# ftdi_modbus_v2.net
KiCad netlist of a schematic drawn in EAGLE
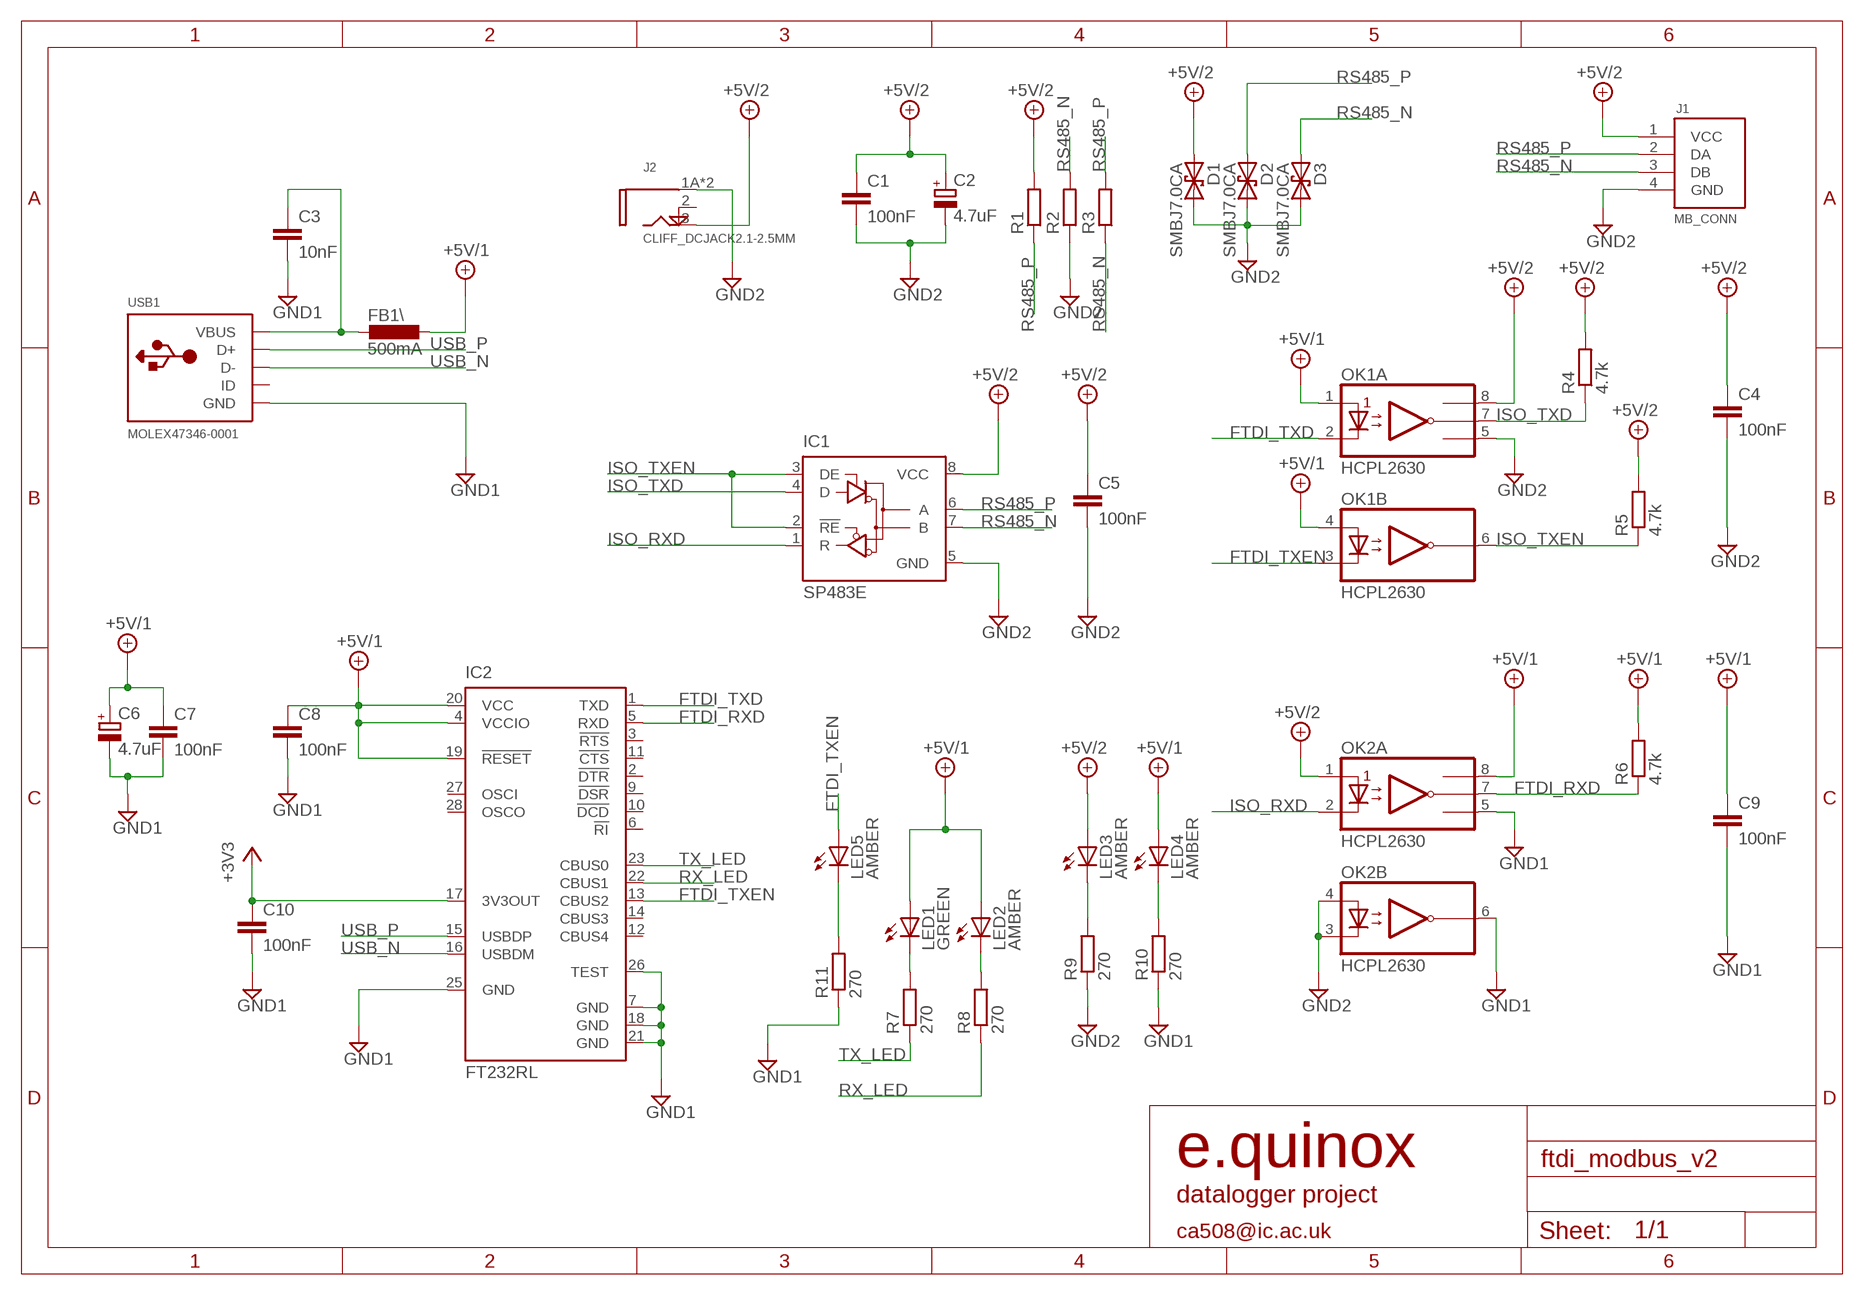
[diagram p0: schematic, sheet 1]

(export (version "E")
  (design (tool "Eeschema 10.0.6"))
  (components
    (comp (ref "C1")
      (value "100nF")
      (footprint "eagle-import:C0603")
      (libsource (lib "eagle-import") (part "C-EUC0603"))
    )
    (comp (ref "C2")
      (value "4.7uF")
      (footprint "eagle-import:B_3528-21R")
      (libsource (lib "eagle-import") (part "CPOL-EUB/3528-21R"))
    )
    (comp (ref "C3")
      (value "10nF")
      (footprint "eagle-import:C0603")
      (libsource (lib "eagle-import") (part "C-EUC0603"))
    )
    (comp (ref "C4")
      (value "100nF")
      (footprint "eagle-import:C1206")
      (libsource (lib "eagle-import") (part "C-EUC1206"))
    )
    (comp (ref "C5")
      (value "100nF")
      (footprint "eagle-import:C0603")
      (libsource (lib "eagle-import") (part "C-EUC0603"))
    )
    (comp (ref "C6")
      (value "4.7uF")
      (footprint "eagle-import:B_3528-21R")
      (libsource (lib "eagle-import") (part "CPOL-EUB/3528-21R"))
    )
    (comp (ref "C7")
      (value "100nF")
      (footprint "eagle-import:C0603")
      (libsource (lib "eagle-import") (part "C-EUC0603"))
    )
    (comp (ref "C8")
      (value "100nF")
      (footprint "eagle-import:C0603")
      (libsource (lib "eagle-import") (part "C-EUC0603"))
    )
    (comp (ref "C9")
      (value "100nF")
      (footprint "eagle-import:C1206")
      (libsource (lib "eagle-import") (part "C-EUC1206"))
    )
    (comp (ref "C10")
      (value "100nF")
      (footprint "eagle-import:C0603")
      (libsource (lib "eagle-import") (part "C-EUC0603"))
    )
    (comp (ref "D1")
      (value "SMBJ7.0CA")
      (footprint "eagle-import:DO214AA")
      (libsource (lib "eagle-import") (part "SMBJ7.0CA"))
    )
    (comp (ref "D2")
      (value "SMBJ7.0CA")
      (footprint "eagle-import:DO214AA")
      (libsource (lib "eagle-import") (part "SMBJ7.0CA"))
    )
    (comp (ref "D3")
      (value "SMBJ7.0CA")
      (footprint "eagle-import:DO214AA")
      (libsource (lib "eagle-import") (part "SMBJ7.0CA"))
    )
    (comp (ref "FB1\\")
      (value "500mA")
      (footprint "eagle-import:L3216C")
      (libsource (lib "eagle-import") (part "L-EUL3216C"))
    )
    (comp (ref "IC1")
      (value "SP483E")
      (footprint "eagle-import:D_R-PDSO-G8")
      (libsource (lib "eagle-import") (part "75176AD"))
    )
    (comp (ref "IC2")
      (value "FT232RL")
      (footprint "eagle-import:SSOP28")
      (libsource (lib "eagle-import") (part "FT232RL"))
    )
    (comp (ref "J1")
      (value "MB_CONN")
      (footprint "eagle-import:PTSM0,5_4-HH-2,5-THR")
      (libsource (lib "eagle-import") (part "MB_CONN"))
    )
    (comp (ref "J2")
      (value "CLIFF_DCJACK2.1-2.5MM")
      (footprint "eagle-import:FC6814XS")
      (libsource (lib "eagle-import") (part "CLIFF_DCJACK2.1-2.5MM"))
    )
    (comp (ref "LED1")
      (value "GREEN")
      (footprint "eagle-import:CHIPLED_0805")
      (libsource (lib "eagle-import") (part "LEDCHIPLED_0805"))
    )
    (comp (ref "LED2")
      (value "AMBER")
      (footprint "eagle-import:CHIPLED_0805")
      (libsource (lib "eagle-import") (part "LEDCHIPLED_0805"))
    )
    (comp (ref "LED3")
      (value "AMBER")
      (footprint "eagle-import:CHIPLED_0805")
      (libsource (lib "eagle-import") (part "LEDCHIPLED_0805"))
    )
    (comp (ref "LED4")
      (value "AMBER")
      (footprint "eagle-import:CHIPLED_0805")
      (libsource (lib "eagle-import") (part "LEDCHIPLED_0805"))
    )
    (comp (ref "LED5")
      (value "AMBER")
      (footprint "eagle-import:CHIPLED_0805")
      (libsource (lib "eagle-import") (part "LEDCHIPLED_0805"))
    )
    (comp (ref "OK1")
      (value "HCPL2630")
      (footprint "eagle-import:DIL08")
      (fields (field (name "MF") "AGILENT TECHNOLOGIES") (field (name "MPN") "HCPL-2630-000E"))
      (libsource (lib "eagle-import") (part "HCPL2630"))
    )
    (comp (ref "OK2")
      (value "HCPL2630")
      (footprint "eagle-import:DIL08")
      (fields (field (name "MF") "AGILENT TECHNOLOGIES") (field (name "MPN") "HCPL-2630-000E"))
      (libsource (lib "eagle-import") (part "HCPL2630"))
    )
    (comp (ref "R1")
      (value "R-EU_0207/10")
      (footprint "eagle-import:0207_10")
      (libsource (lib "eagle-import") (part "R-EU_0207/10"))
    )
    (comp (ref "R2")
      (value "R-EU_0207/10")
      (footprint "eagle-import:0207_10")
      (libsource (lib "eagle-import") (part "R-EU_0207/10"))
    )
    (comp (ref "R3")
      (value "R-EU_0207/10")
      (footprint "eagle-import:0207_10")
      (libsource (lib "eagle-import") (part "R-EU_0207/10"))
    )
    (comp (ref "R4")
      (value "4.7k")
      (footprint "eagle-import:M0805")
      (libsource (lib "eagle-import") (part "R-EU_M0805"))
    )
    (comp (ref "R5")
      (value "4.7k")
      (footprint "eagle-import:M0805")
      (libsource (lib "eagle-import") (part "R-EU_M0805"))
    )
    (comp (ref "R6")
      (value "4.7k")
      (footprint "eagle-import:M0805")
      (libsource (lib "eagle-import") (part "R-EU_M0805"))
    )
    (comp (ref "R7")
      (value "270")
      (footprint "eagle-import:M0805")
      (libsource (lib "eagle-import") (part "R-EU_M0805"))
    )
    (comp (ref "R8")
      (value "270")
      (footprint "eagle-import:M0805")
      (libsource (lib "eagle-import") (part "R-EU_M0805"))
    )
    (comp (ref "R9")
      (value "270")
      (footprint "eagle-import:M0805")
      (libsource (lib "eagle-import") (part "R-EU_M0805"))
    )
    (comp (ref "R10")
      (value "270")
      (footprint "eagle-import:M0805")
      (libsource (lib "eagle-import") (part "R-EU_M0805"))
    )
    (comp (ref "R11")
      (value "270")
      (footprint "eagle-import:M0805")
      (libsource (lib "eagle-import") (part "R-EU_M0805"))
    )
    (comp (ref "USB1")
      (value "MOLEX47346-0001")
      (footprint "eagle-import:47346-0001")
      (libsource (lib "eagle-import") (part "MOLEX47346-0001"))
    )
  )
  (nets
    (net (code "1") (name "+3V3") (class "Default")
      (node (ref "C10") (pin "1") (pinfunction "1_1") (pintype "passive"))
      (node (ref "IC2") (pin "17") (pinfunction "3V3OUT_17") (pintype "output"))
    )
    (net (code "2") (name "+5V{slash}1") (class "Default")
      (node (ref "C6") (pin "+") (pinfunction "+_+") (pintype "passive"))
      (node (ref "C7") (pin "1") (pinfunction "1_1") (pintype "passive"))
      (node (ref "C8") (pin "1") (pinfunction "1_1") (pintype "passive"))
      (node (ref "C9") (pin "1") (pinfunction "1_1") (pintype "passive"))
      (node (ref "FB1\\") (pin "1") (pinfunction "1_1") (pintype "passive"))
      (node (ref "IC2") (pin "19") (pinfunction "~{RESET}_19") (pintype "input"))
      (node (ref "IC2") (pin "20") (pinfunction "VCC_20") (pintype "power_in"))
      (node (ref "IC2") (pin "4") (pinfunction "VCCIO_4") (pintype "power_in"))
      (node (ref "LED1") (pin "A") (pinfunction "A_A") (pintype "passive"))
      (node (ref "LED2") (pin "A") (pinfunction "A_A") (pintype "passive"))
      (node (ref "LED4") (pin "A") (pinfunction "A_A") (pintype "passive"))
      (node (ref "OK1") (pin "1") (pinfunction "A1_1") (pintype "passive"))
      (node (ref "OK1") (pin "4") (pinfunction "A2_4") (pintype "passive"))
      (node (ref "OK2") (pin "8") (pinfunction "VCC_8") (pintype "passive"))
      (node (ref "R6") (pin "2") (pinfunction "2_2") (pintype "passive"))
    )
    (net (code "3") (name "+5V{slash}2") (class "Default")
      (node (ref "C1") (pin "1") (pinfunction "1_1") (pintype "passive"))
      (node (ref "C2") (pin "+") (pinfunction "+_+") (pintype "passive"))
      (node (ref "C4") (pin "1") (pinfunction "1_1") (pintype "passive"))
      (node (ref "C5") (pin "1") (pinfunction "1_1") (pintype "passive"))
      (node (ref "D1") (pin "P$1") (pinfunction "1_P$1") (pintype "passive"))
      (node (ref "IC1") (pin "8") (pinfunction "VCC_8") (pintype "power_in"))
      (node (ref "J1") (pin "1") (pinfunction "VCC_1") (pintype "power_in"))
      (node (ref "J2") (pin "3") (pinfunction "TIP_3") (pintype "power_in"))
      (node (ref "LED3") (pin "A") (pinfunction "A_A") (pintype "passive"))
      (node (ref "OK1") (pin "8") (pinfunction "VCC_8") (pintype "passive"))
      (node (ref "OK2") (pin "1") (pinfunction "A1_1") (pintype "passive"))
      (node (ref "R1") (pin "2") (pinfunction "2_2") (pintype "passive"))
      (node (ref "R4") (pin "2") (pinfunction "2_2") (pintype "passive"))
      (node (ref "R5") (pin "2") (pinfunction "2_2") (pintype "passive"))
    )
    (net (code "4") (name "/FTDI_RXD") (class "Default")
      (node (ref "IC2") (pin "5") (pinfunction "RXD_5") (pintype "input"))
      (node (ref "OK2") (pin "7") (pinfunction "VO1_7") (pintype "passive"))
      (node (ref "R6") (pin "1") (pinfunction "1_1") (pintype "passive"))
    )
    (net (code "5") (name "/FTDI_TXD") (class "Default")
      (node (ref "IC2") (pin "1") (pinfunction "TXD_1") (pintype "output"))
      (node (ref "OK1") (pin "2") (pinfunction "C1_2") (pintype "passive"))
    )
    (net (code "6") (name "/FTDI_TXEN") (class "Default")
      (node (ref "IC2") (pin "13") (pinfunction "CBUS2_13") (pintype "bidirectional"))
      (node (ref "LED5") (pin "A") (pinfunction "A_A") (pintype "passive"))
      (node (ref "OK1") (pin "3") (pinfunction "C2_3") (pintype "passive"))
    )
    (net (code "7") (name "/ISO_RXD") (class "Default")
      (node (ref "IC1") (pin "1") (pinfunction "R_1") (pintype "input"))
      (node (ref "OK2") (pin "2") (pinfunction "C1_2") (pintype "passive"))
    )
    (net (code "8") (name "/ISO_TXD") (class "Default")
      (node (ref "IC1") (pin "4") (pinfunction "D_4") (pintype "input"))
      (node (ref "OK1") (pin "7") (pinfunction "VO1_7") (pintype "passive"))
      (node (ref "R4") (pin "1") (pinfunction "1_1") (pintype "passive"))
    )
    (net (code "9") (name "/ISO_TXEN") (class "Default")
      (node (ref "IC1") (pin "2") (pinfunction "~{RE}_2") (pintype "input"))
      (node (ref "IC1") (pin "3") (pinfunction "DE_3") (pintype "input"))
      (node (ref "OK1") (pin "6") (pinfunction "VO2_6") (pintype "passive"))
      (node (ref "R5") (pin "1") (pinfunction "1_1") (pintype "passive"))
    )
    (net (code "10") (name "/RS485_N") (class "Default")
      (node (ref "D3") (pin "P$1") (pinfunction "1_P$1") (pintype "passive"))
      (node (ref "IC1") (pin "7") (pinfunction "B_7") (pintype "output"))
      (node (ref "J1") (pin "3") (pinfunction "DB_3") (pintype "bidirectional"))
      (node (ref "R2") (pin "2") (pinfunction "2_2") (pintype "passive"))
      (node (ref "R3") (pin "1") (pinfunction "1_1") (pintype "passive"))
    )
    (net (code "11") (name "/RS485_P") (class "Default")
      (node (ref "D2") (pin "P$1") (pinfunction "1_P$1") (pintype "passive"))
      (node (ref "IC1") (pin "6") (pinfunction "A_6") (pintype "output"))
      (node (ref "J1") (pin "2") (pinfunction "DA_2") (pintype "bidirectional"))
      (node (ref "R1") (pin "1") (pinfunction "1_1") (pintype "passive"))
      (node (ref "R3") (pin "2") (pinfunction "2_2") (pintype "passive"))
    )
    (net (code "12") (name "/RX_LED") (class "Default")
      (node (ref "IC2") (pin "22") (pinfunction "CBUS1_22") (pintype "bidirectional"))
      (node (ref "R8") (pin "1") (pinfunction "1_1") (pintype "passive"))
    )
    (net (code "13") (name "/SHUNT") (class "Default")
      (node (ref "J2") (pin "2") (pinfunction "SHUNT_2") (pintype "power_in"))
    )
    (net (code "14") (name "/TX_LED") (class "Default")
      (node (ref "IC2") (pin "23") (pinfunction "CBUS0_23") (pintype "bidirectional"))
      (node (ref "R7") (pin "1") (pinfunction "1_1") (pintype "passive"))
    )
    (net (code "15") (name "/USB_N") (class "Default")
      (node (ref "IC2") (pin "16") (pinfunction "USBDM_16") (pintype "bidirectional"))
      (node (ref "USB1") (pin "2") (pinfunction "D-_2") (pintype "bidirectional"))
    )
    (net (code "16") (name "/USB_P") (class "Default")
      (node (ref "IC2") (pin "15") (pinfunction "USBDP_15") (pintype "bidirectional"))
      (node (ref "USB1") (pin "3") (pinfunction "D+_3") (pintype "bidirectional"))
    )
    (net (code "17") (name "GND1") (class "Default")
      (node (ref "C10") (pin "2") (pinfunction "2_2") (pintype "passive"))
      (node (ref "C3") (pin "2") (pinfunction "2_2") (pintype "passive"))
      (node (ref "C6") (pin "-") (pinfunction "-_-") (pintype "passive"))
      (node (ref "C7") (pin "2") (pinfunction "2_2") (pintype "passive"))
      (node (ref "C8") (pin "2") (pinfunction "2_2") (pintype "passive"))
      (node (ref "C9") (pin "2") (pinfunction "2_2") (pintype "passive"))
      (node (ref "IC2") (pin "18") (pinfunction "GND_18") (pintype "power_in"))
      (node (ref "IC2") (pin "21") (pinfunction "GND_21") (pintype "power_in"))
      (node (ref "IC2") (pin "25") (pinfunction "GND_25") (pintype "power_in"))
      (node (ref "IC2") (pin "26") (pinfunction "TEST_26") (pintype "input"))
      (node (ref "IC2") (pin "7") (pinfunction "GND_7") (pintype "power_in"))
      (node (ref "OK2") (pin "5") (pinfunction "GND_5") (pintype "passive"))
      (node (ref "OK2") (pin "6") (pinfunction "VO2_6") (pintype "passive"))
      (node (ref "R10") (pin "1") (pinfunction "1_1") (pintype "passive"))
      (node (ref "R11") (pin "1") (pinfunction "1_1") (pintype "passive"))
      (node (ref "USB1") (pin "5") (pinfunction "GND_5") (pintype "power_in"))
    )
    (net (code "18") (name "GND2") (class "Default")
      (node (ref "C1") (pin "2") (pinfunction "2_2") (pintype "passive"))
      (node (ref "C2") (pin "-") (pinfunction "-_-") (pintype "passive"))
      (node (ref "C4") (pin "2") (pinfunction "2_2") (pintype "passive"))
      (node (ref "C5") (pin "2") (pinfunction "2_2") (pintype "passive"))
      (node (ref "D1") (pin "P$2") (pinfunction "2_P$2") (pintype "passive"))
      (node (ref "D2") (pin "P$2") (pinfunction "2_P$2") (pintype "passive"))
      (node (ref "D3") (pin "P$2") (pinfunction "2_P$2") (pintype "passive"))
      (node (ref "IC1") (pin "5") (pinfunction "GND_5") (pintype "power_in"))
      (node (ref "J1") (pin "4") (pinfunction "GND_4") (pintype "passive"))
      (node (ref "J2") (pin "1A") (pinfunction "SLEEVE_1A") (pintype "power_in"))
      (node (ref "J2") (pin "1B") (pinfunction "SLEEVE_1B") (pintype "power_in"))
      (node (ref "OK1") (pin "5") (pinfunction "GND_5") (pintype "passive"))
      (node (ref "OK2") (pin "3") (pinfunction "C2_3") (pintype "passive"))
      (node (ref "OK2") (pin "4") (pinfunction "A2_4") (pintype "passive"))
      (node (ref "R2") (pin "1") (pinfunction "1_1") (pintype "passive"))
      (node (ref "R9") (pin "1") (pinfunction "1_1") (pintype "passive"))
    )
    (net (code "19") (name "Net-(LED1-PadC)") (class "Default")
      (node (ref "LED1") (pin "C") (pinfunction "C_C") (pintype "passive"))
      (node (ref "R7") (pin "2") (pinfunction "2_2") (pintype "passive"))
    )
    (net (code "20") (name "Net-(LED2-PadC)") (class "Default")
      (node (ref "LED2") (pin "C") (pinfunction "C_C") (pintype "passive"))
      (node (ref "R8") (pin "2") (pinfunction "2_2") (pintype "passive"))
    )
    (net (code "21") (name "Net-(LED3-PadC)") (class "Default")
      (node (ref "LED3") (pin "C") (pinfunction "C_C") (pintype "passive"))
      (node (ref "R9") (pin "2") (pinfunction "2_2") (pintype "passive"))
    )
    (net (code "22") (name "Net-(LED4-PadC)") (class "Default")
      (node (ref "LED4") (pin "C") (pinfunction "C_C") (pintype "passive"))
      (node (ref "R10") (pin "2") (pinfunction "2_2") (pintype "passive"))
    )
    (net (code "23") (name "Net-(LED5-PadC)") (class "Default")
      (node (ref "LED5") (pin "C") (pinfunction "C_C") (pintype "passive"))
      (node (ref "R11") (pin "2") (pinfunction "2_2") (pintype "passive"))
    )
    (net (code "24") (name "Net-(USB1-VBUS)") (class "Default")
      (node (ref "C3") (pin "1") (pinfunction "1_1") (pintype "passive"))
      (node (ref "FB1\\") (pin "2") (pinfunction "2_2") (pintype "passive"))
      (node (ref "USB1") (pin "1") (pinfunction "VBUS_1") (pintype "power_in"))
    )
    (net (code "25") (name "unconnected-(IC2-CBUS3-Pad14)") (class "Default")
      (node (ref "IC2") (pin "14") (pinfunction "CBUS3_14") (pintype "bidirectional"))
    )
    (net (code "26") (name "unconnected-(IC2-CBUS4-Pad12)") (class "Default")
      (node (ref "IC2") (pin "12") (pinfunction "CBUS4_12") (pintype "bidirectional"))
    )
    (net (code "27") (name "unconnected-(IC2-OSCI-Pad27)") (class "Default")
      (node (ref "IC2") (pin "27") (pinfunction "OSCI_27") (pintype "input"))
    )
    (net (code "28") (name "unconnected-(IC2-OSCO-Pad28)") (class "Default")
      (node (ref "IC2") (pin "28") (pinfunction "OSCO_28") (pintype "output"))
    )
    (net (code "29") (name "unconnected-(IC2-~{CTS}-Pad11)") (class "Default")
      (node (ref "IC2") (pin "11") (pinfunction "~{CTS}_11") (pintype "input"))
    )
    (net (code "30") (name "unconnected-(IC2-~{DCD}-Pad10)") (class "Default")
      (node (ref "IC2") (pin "10") (pinfunction "~{DCD}_10") (pintype "input"))
    )
    (net (code "31") (name "unconnected-(IC2-~{DSR}-Pad9)") (class "Default")
      (node (ref "IC2") (pin "9") (pinfunction "~{DSR}_9") (pintype "input"))
    )
    (net (code "32") (name "unconnected-(IC2-~{DTR}-Pad2)") (class "Default")
      (node (ref "IC2") (pin "2") (pinfunction "~{DTR}_2") (pintype "output"))
    )
    (net (code "33") (name "unconnected-(IC2-~{RI}-Pad6)") (class "Default")
      (node (ref "IC2") (pin "6") (pinfunction "~{RI}_6") (pintype "input"))
    )
    (net (code "34") (name "unconnected-(IC2-~{RTS}-Pad3)") (class "Default")
      (node (ref "IC2") (pin "3") (pinfunction "~{RTS}_3") (pintype "output"))
    )
    (net (code "35") (name "unconnected-(USB1-ID-Pad4)") (class "Default")
      (node (ref "USB1") (pin "4") (pinfunction "ID_4") (pintype "bidirectional"))
    )
  )
)
